# GigaVGA666.net
KiCad netlist of a schematic drawn in EasyEDA Pro
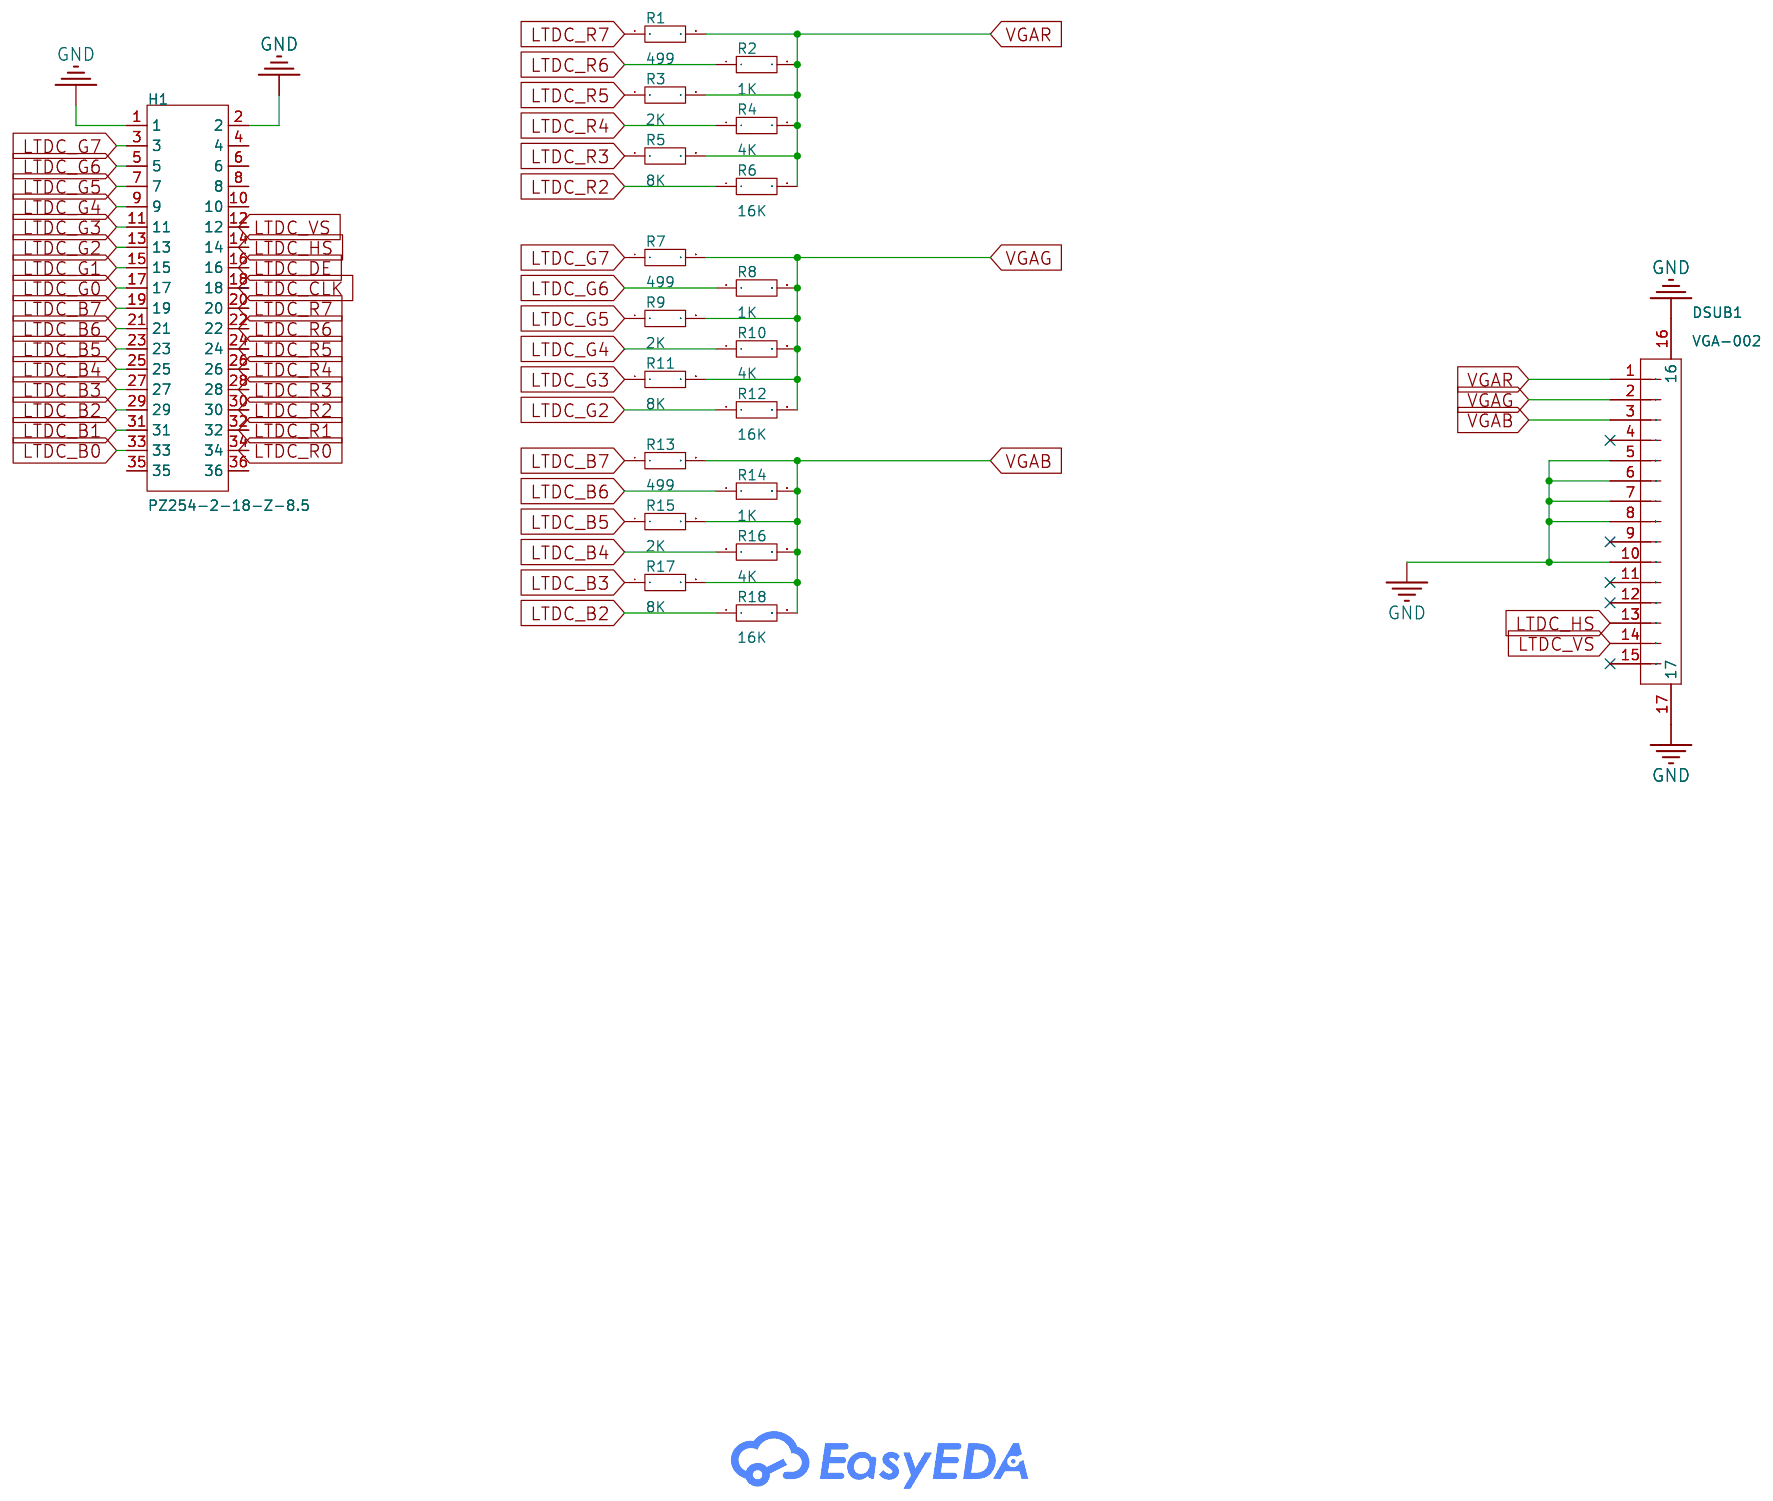
[diagram p0: schematic sheet]

(export (version "E")
  (design (tool "Eeschema 10.0.6"))
  (components
    (comp (ref "DSUB1")
      (value "VGA-002")
      (footprint "easyedapro:D-SUB-TH_VGA-002")
      (fields (field (name "Manufacturer") "BOOMELE(博穆精密)"))
      (libsource (lib "easyedapro") (part "VGA-002"))
    )
    (comp (ref "H1")
      (value "PZ254-2-18-Z-8.5")
      (footprint "easyedapro:HDR-TH_36P-P2.54-V-M-R2-C18-S2.54")
      (fields (field (name "Manufacturer") "HCTL(华灿天禄)"))
      (libsource (lib "easyedapro") (part "PZ254-2-18-Z-8.5"))
    )
    (comp (ref "R1") (value "499") (footprint "easyedapro:R0603") (libsource (lib "easyedapro") (part "Res")))
    (comp (ref "R2") (value "1K") (footprint "easyedapro:R0603") (libsource (lib "easyedapro") (part "Res")))
    (comp (ref "R3") (value "2K") (footprint "easyedapro:R0603") (libsource (lib "easyedapro") (part "Res")))
    (comp (ref "R4") (value "4K") (footprint "easyedapro:R0603") (libsource (lib "easyedapro") (part "Res")))
    (comp (ref "R5") (value "8K") (footprint "easyedapro:R0603") (libsource (lib "easyedapro") (part "Res")))
    (comp (ref "R6") (value "16K") (footprint "easyedapro:R0603") (libsource (lib "easyedapro") (part "Res")))
    (comp (ref "R7") (value "499") (footprint "easyedapro:R0603") (libsource (lib "easyedapro") (part "Res")))
    (comp (ref "R8") (value "1K") (footprint "easyedapro:R0603") (libsource (lib "easyedapro") (part "Res")))
    (comp (ref "R9") (value "2K") (footprint "easyedapro:R0603") (libsource (lib "easyedapro") (part "Res")))
    (comp (ref "R10") (value "4K") (footprint "easyedapro:R0603") (libsource (lib "easyedapro") (part "Res")))
    (comp (ref "R11") (value "8K") (footprint "easyedapro:R0603") (libsource (lib "easyedapro") (part "Res")))
    (comp (ref "R12")
      (value "16K")
      (footprint "easyedapro:R0603")
      (libsource (lib "easyedapro") (part "Res"))
    )
    (comp (ref "R13")
      (value "499")
      (footprint "easyedapro:R0603")
      (libsource (lib "easyedapro") (part "Res"))
    )
    (comp (ref "R14") (value "1K") (footprint "easyedapro:R0603") (libsource (lib "easyedapro") (part "Res")))
    (comp (ref "R15") (value "2K") (footprint "easyedapro:R0603") (libsource (lib "easyedapro") (part "Res")))
    (comp (ref "R16") (value "4K") (footprint "easyedapro:R0603") (libsource (lib "easyedapro") (part "Res")))
    (comp (ref "R17") (value "8K") (footprint "easyedapro:R0603") (libsource (lib "easyedapro") (part "Res")))
    (comp (ref "R18")
      (value "16K")
      (footprint "easyedapro:R0603")
      (libsource (lib "easyedapro") (part "Res"))
    )
  )
  (nets
    (net (code "1") (name "GND") (class "Default")
      (node (ref "DSUB1") (pin "10") (pinfunction "10_10") (pintype "unspecified"))
      (node (ref "DSUB1") (pin "16") (pinfunction "16_16") (pintype "unspecified"))
      (node (ref "DSUB1") (pin "17") (pinfunction "17_17") (pintype "unspecified"))
      (node (ref "DSUB1") (pin "5") (pinfunction "5_5") (pintype "unspecified"))
      (node (ref "DSUB1") (pin "6") (pinfunction "6_6") (pintype "unspecified"))
      (node (ref "DSUB1") (pin "7") (pinfunction "7_7") (pintype "unspecified"))
      (node (ref "DSUB1") (pin "8") (pinfunction "8_8") (pintype "unspecified"))
      (node (ref "H1") (pin "1") (pinfunction "1_1") (pintype "unspecified"))
      (node (ref "H1") (pin "2") (pinfunction "2_2") (pintype "unspecified"))
    )
    (net (code "2") (name "LTDC_B0") (class "Default")
      (node (ref "H1") (pin "33") (pinfunction "33_33") (pintype "unspecified"))
    )
    (net (code "3") (name "LTDC_B1") (class "Default")
      (node (ref "H1") (pin "31") (pinfunction "31_31") (pintype "unspecified"))
    )
    (net (code "4") (name "LTDC_B2") (class "Default")
      (node (ref "H1") (pin "29") (pinfunction "29_29") (pintype "unspecified"))
      (node (ref "R18") (pin "1") (pinfunction "1_1") (pintype "input"))
    )
    (net (code "5") (name "LTDC_B3") (class "Default")
      (node (ref "H1") (pin "27") (pinfunction "27_27") (pintype "unspecified"))
      (node (ref "R17") (pin "1") (pinfunction "1_1") (pintype "input"))
    )
    (net (code "6") (name "LTDC_B4") (class "Default")
      (node (ref "H1") (pin "25") (pinfunction "25_25") (pintype "unspecified"))
      (node (ref "R16") (pin "1") (pinfunction "1_1") (pintype "input"))
    )
    (net (code "7") (name "LTDC_B5") (class "Default")
      (node (ref "H1") (pin "23") (pinfunction "23_23") (pintype "unspecified"))
      (node (ref "R15") (pin "1") (pinfunction "1_1") (pintype "input"))
    )
    (net (code "8") (name "LTDC_B6") (class "Default")
      (node (ref "H1") (pin "21") (pinfunction "21_21") (pintype "unspecified"))
      (node (ref "R14") (pin "1") (pinfunction "1_1") (pintype "input"))
    )
    (net (code "9") (name "LTDC_B7") (class "Default")
      (node (ref "H1") (pin "19") (pinfunction "19_19") (pintype "unspecified"))
      (node (ref "R13") (pin "1") (pinfunction "1_1") (pintype "input"))
    )
    (net (code "10") (name "LTDC_CLK") (class "Default")
      (node (ref "H1") (pin "18") (pinfunction "18_18") (pintype "unspecified"))
    )
    (net (code "11") (name "LTDC_DE") (class "Default")
      (node (ref "H1") (pin "16") (pinfunction "16_16") (pintype "unspecified"))
    )
    (net (code "12") (name "LTDC_G0") (class "Default")
      (node (ref "H1") (pin "17") (pinfunction "17_17") (pintype "unspecified"))
    )
    (net (code "13") (name "LTDC_G1") (class "Default")
      (node (ref "H1") (pin "15") (pinfunction "15_15") (pintype "unspecified"))
    )
    (net (code "14") (name "LTDC_G2") (class "Default")
      (node (ref "H1") (pin "13") (pinfunction "13_13") (pintype "unspecified"))
      (node (ref "R12") (pin "1") (pinfunction "1_1") (pintype "input"))
    )
    (net (code "15") (name "LTDC_G3") (class "Default")
      (node (ref "H1") (pin "11") (pinfunction "11_11") (pintype "unspecified"))
      (node (ref "R11") (pin "1") (pinfunction "1_1") (pintype "input"))
    )
    (net (code "16") (name "LTDC_G4") (class "Default")
      (node (ref "H1") (pin "9") (pinfunction "9_9") (pintype "unspecified"))
      (node (ref "R10") (pin "1") (pinfunction "1_1") (pintype "input"))
    )
    (net (code "17") (name "LTDC_G5") (class "Default")
      (node (ref "H1") (pin "7") (pinfunction "7_7") (pintype "unspecified"))
      (node (ref "R9") (pin "1") (pinfunction "1_1") (pintype "input"))
    )
    (net (code "18") (name "LTDC_G6") (class "Default")
      (node (ref "H1") (pin "5") (pinfunction "5_5") (pintype "unspecified"))
      (node (ref "R8") (pin "1") (pinfunction "1_1") (pintype "input"))
    )
    (net (code "19") (name "LTDC_G7") (class "Default")
      (node (ref "H1") (pin "3") (pinfunction "3_3") (pintype "unspecified"))
      (node (ref "R7") (pin "1") (pinfunction "1_1") (pintype "input"))
    )
    (net (code "20") (name "LTDC_HS") (class "Default")
      (node (ref "DSUB1") (pin "13") (pinfunction "13_13") (pintype "unspecified"))
      (node (ref "H1") (pin "14") (pinfunction "14_14") (pintype "unspecified"))
    )
    (net (code "21") (name "LTDC_R0") (class "Default")
      (node (ref "H1") (pin "34") (pinfunction "34_34") (pintype "unspecified"))
    )
    (net (code "22") (name "LTDC_R1") (class "Default")
      (node (ref "H1") (pin "32") (pinfunction "32_32") (pintype "unspecified"))
    )
    (net (code "23") (name "LTDC_R2") (class "Default")
      (node (ref "H1") (pin "30") (pinfunction "30_30") (pintype "unspecified"))
      (node (ref "R6") (pin "1") (pinfunction "1_1") (pintype "input"))
    )
    (net (code "24") (name "LTDC_R3") (class "Default")
      (node (ref "H1") (pin "28") (pinfunction "28_28") (pintype "unspecified"))
      (node (ref "R5") (pin "1") (pinfunction "1_1") (pintype "input"))
    )
    (net (code "25") (name "LTDC_R4") (class "Default")
      (node (ref "H1") (pin "26") (pinfunction "26_26") (pintype "unspecified"))
      (node (ref "R4") (pin "1") (pinfunction "1_1") (pintype "input"))
    )
    (net (code "26") (name "LTDC_R5") (class "Default")
      (node (ref "H1") (pin "24") (pinfunction "24_24") (pintype "unspecified"))
      (node (ref "R3") (pin "1") (pinfunction "1_1") (pintype "input"))
    )
    (net (code "27") (name "LTDC_R6") (class "Default")
      (node (ref "H1") (pin "22") (pinfunction "22_22") (pintype "unspecified"))
      (node (ref "R2") (pin "1") (pinfunction "1_1") (pintype "input"))
    )
    (net (code "28") (name "LTDC_R7") (class "Default")
      (node (ref "H1") (pin "20") (pinfunction "20_20") (pintype "unspecified"))
      (node (ref "R1") (pin "1") (pinfunction "1_1") (pintype "input"))
    )
    (net (code "29") (name "LTDC_VS") (class "Default")
      (node (ref "DSUB1") (pin "14") (pinfunction "14_14") (pintype "unspecified"))
      (node (ref "H1") (pin "12") (pinfunction "12_12") (pintype "unspecified"))
    )
    (net (code "30") (name "VGAB") (class "Default")
      (node (ref "DSUB1") (pin "3") (pinfunction "3_3") (pintype "unspecified"))
      (node (ref "R13") (pin "2") (pinfunction "2_2") (pintype "input"))
      (node (ref "R14") (pin "2") (pinfunction "2_2") (pintype "input"))
      (node (ref "R15") (pin "2") (pinfunction "2_2") (pintype "input"))
      (node (ref "R16") (pin "2") (pinfunction "2_2") (pintype "input"))
      (node (ref "R17") (pin "2") (pinfunction "2_2") (pintype "input"))
      (node (ref "R18") (pin "2") (pinfunction "2_2") (pintype "input"))
    )
    (net (code "31") (name "VGAG") (class "Default")
      (node (ref "DSUB1") (pin "2") (pinfunction "2_2") (pintype "unspecified"))
      (node (ref "R10") (pin "2") (pinfunction "2_2") (pintype "input"))
      (node (ref "R11") (pin "2") (pinfunction "2_2") (pintype "input"))
      (node (ref "R12") (pin "2") (pinfunction "2_2") (pintype "input"))
      (node (ref "R7") (pin "2") (pinfunction "2_2") (pintype "input"))
      (node (ref "R8") (pin "2") (pinfunction "2_2") (pintype "input"))
      (node (ref "R9") (pin "2") (pinfunction "2_2") (pintype "input"))
    )
    (net (code "32") (name "VGAR") (class "Default")
      (node (ref "DSUB1") (pin "1") (pinfunction "1_1") (pintype "unspecified"))
      (node (ref "R1") (pin "2") (pinfunction "2_2") (pintype "input"))
      (node (ref "R2") (pin "2") (pinfunction "2_2") (pintype "input"))
      (node (ref "R3") (pin "2") (pinfunction "2_2") (pintype "input"))
      (node (ref "R4") (pin "2") (pinfunction "2_2") (pintype "input"))
      (node (ref "R5") (pin "2") (pinfunction "2_2") (pintype "input"))
      (node (ref "R6") (pin "2") (pinfunction "2_2") (pintype "input"))
    )
    (net (code "33") (name "unconnected-(DSUB1-Pad4)") (class "Default")
      (node (ref "DSUB1") (pin "4") (pinfunction "4_4") (pintype "unspecified+no_connect"))
    )
    (net (code "34") (name "unconnected-(DSUB1-Pad9)") (class "Default")
      (node (ref "DSUB1") (pin "9") (pinfunction "9_9") (pintype "unspecified+no_connect"))
    )
    (net (code "35") (name "unconnected-(DSUB1-Pad11)") (class "Default")
      (node (ref "DSUB1") (pin "11") (pinfunction "11_11") (pintype "unspecified+no_connect"))
    )
    (net (code "36") (name "unconnected-(DSUB1-Pad12)") (class "Default")
      (node (ref "DSUB1") (pin "12") (pinfunction "12_12") (pintype "unspecified+no_connect"))
    )
    (net (code "37") (name "unconnected-(DSUB1-Pad15)") (class "Default")
      (node (ref "DSUB1") (pin "15") (pinfunction "15_15") (pintype "unspecified+no_connect"))
    )
    (net (code "38") (name "unconnected-(H1-Pad4)") (class "Default")
      (node (ref "H1") (pin "4") (pinfunction "4_4") (pintype "unspecified"))
    )
    (net (code "39") (name "unconnected-(H1-Pad6)") (class "Default")
      (node (ref "H1") (pin "6") (pinfunction "6_6") (pintype "unspecified"))
    )
    (net (code "40") (name "unconnected-(H1-Pad8)") (class "Default")
      (node (ref "H1") (pin "8") (pinfunction "8_8") (pintype "unspecified"))
    )
    (net (code "41") (name "unconnected-(H1-Pad10)") (class "Default")
      (node (ref "H1") (pin "10") (pinfunction "10_10") (pintype "unspecified"))
    )
    (net (code "42") (name "unconnected-(H1-Pad35)") (class "Default")
      (node (ref "H1") (pin "35") (pinfunction "35_35") (pintype "unspecified"))
    )
    (net (code "43") (name "unconnected-(H1-Pad36)") (class "Default")
      (node (ref "H1") (pin "36") (pinfunction "36_36") (pintype "unspecified"))
    )
  )
)
